# battery_monitor.net
KiCad netlist of a schematic drawn in EAGLE
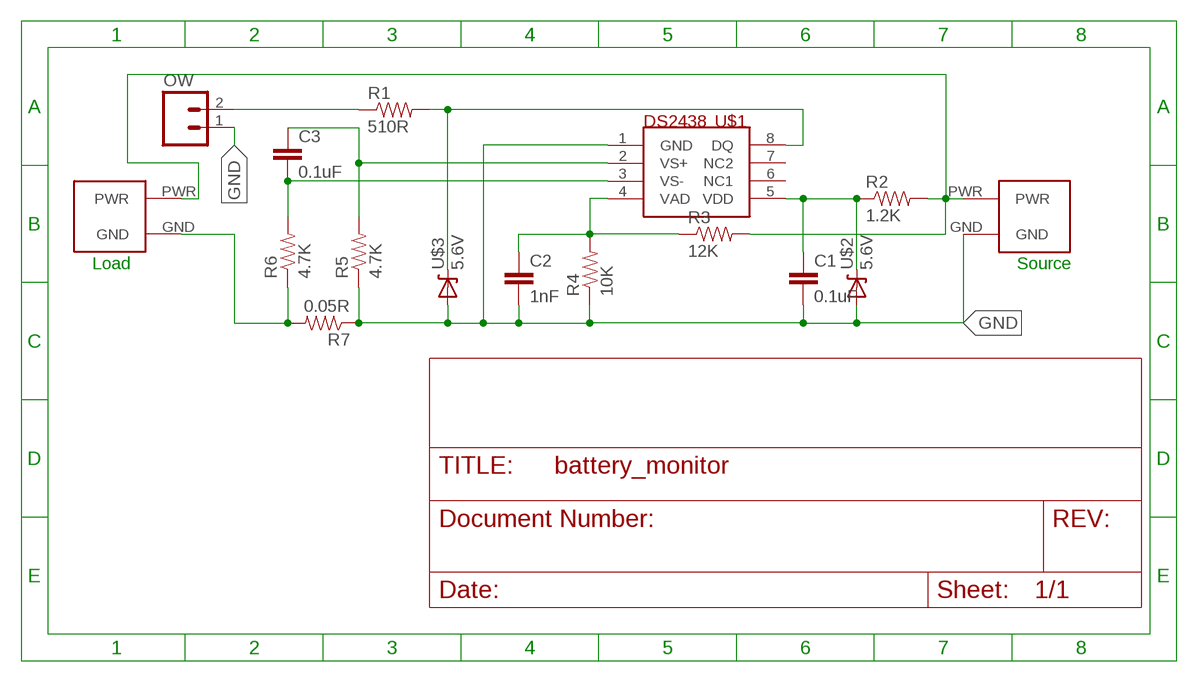
[diagram p0: schematic, sheet 1]

(export (version "E")
  (design (tool "Eeschema 10.0.6"))
  (components
    (comp (ref "C1")
      (value "0.1uF")
      (footprint "eagle-import:0805")
      (libsource (lib "eagle-import") (part "CAP0805"))
    )
    (comp (ref "C2")
      (value "1nF")
      (footprint "eagle-import:0805")
      (libsource (lib "eagle-import") (part "CAP0805"))
    )
    (comp (ref "C3")
      (value "0.1uF")
      (footprint "eagle-import:0805")
      (libsource (lib "eagle-import") (part "CAP0805"))
    )
    (comp (ref "LOAD")
      (value "AND_PWR")
      (footprint "eagle-import:AND_PWR")
      (libsource (lib "eagle-import") (part "AND_PWR"))
    )
    (comp (ref "OW")
      (value "M02POLAR_LOCK")
      (footprint "eagle-import:MOLEX-1X2_LOCK")
      (libsource (lib "eagle-import") (part "M02POLAR_LOCK"))
    )
    (comp (ref "R1")
      (value "510R")
      (footprint "eagle-import:0805")
      (libsource (lib "eagle-import") (part "RESISTOR0805-RES"))
    )
    (comp (ref "R2")
      (value "1.2K")
      (footprint "eagle-import:0805")
      (libsource (lib "eagle-import") (part "RESISTOR0805-RES"))
    )
    (comp (ref "R3")
      (value "12K")
      (footprint "eagle-import:0805")
      (libsource (lib "eagle-import") (part "RESISTOR0805-RES"))
    )
    (comp (ref "R4")
      (value "10K")
      (footprint "eagle-import:0805")
      (libsource (lib "eagle-import") (part "RESISTOR0805-RES"))
    )
    (comp (ref "R5")
      (value "4.7K")
      (footprint "eagle-import:0805")
      (libsource (lib "eagle-import") (part "RESISTOR0805-RES"))
    )
    (comp (ref "R6")
      (value "4.7K")
      (footprint "eagle-import:0805")
      (libsource (lib "eagle-import") (part "RESISTOR0805-RES"))
    )
    (comp (ref "R7")
      (value "0.05R")
      (footprint "eagle-import:1206")
      (libsource (lib "eagle-import") (part "RESISTOR1206"))
    )
    (comp (ref "SOURCE")
      (value "AND_PWR")
      (footprint "eagle-import:AND_PWR")
      (libsource (lib "eagle-import") (part "AND_PWR"))
    )
    (comp (ref "U$1")
      (value "DS2438Z")
      (footprint "eagle-import:SOIC8")
      (libsource (lib "eagle-import") (part "DS2438Z"))
    )
    (comp (ref "U$2")
      (value "5.6V")
      (footprint "eagle-import:SMB-DIODE")
      (libsource (lib "eagle-import") (part "DIODE-ZENERSMB"))
    )
    (comp (ref "U$3")
      (value "5.6V")
      (footprint "eagle-import:SMB-DIODE")
      (libsource (lib "eagle-import") (part "DIODE-ZENERSMB"))
    )
  )
  (nets
    (net (code "1") (name "GND") (class "Default")
      (node (ref "C1") (pin "2") (pinfunction "2_2") (pintype "passive"))
      (node (ref "C2") (pin "2") (pinfunction "2_2") (pintype "passive"))
      (node (ref "OW") (pin "1") (pinfunction "1_1") (pintype "passive"))
      (node (ref "R4") (pin "1") (pinfunction "1_1") (pintype "passive"))
      (node (ref "R5") (pin "1") (pinfunction "1_1") (pintype "passive"))
      (node (ref "R7") (pin "1") (pinfunction "1_1") (pintype "passive"))
      (node (ref "SOURCE") (pin "GND") (pinfunction "GND_GND") (pintype "bidirectional"))
      (node (ref "U$1") (pin "1") (pinfunction "GND_1") (pintype "power_in"))
      (node (ref "U$2") (pin "A") (pinfunction "A_A") (pintype "passive"))
      (node (ref "U$3") (pin "A") (pinfunction "A_A") (pintype "passive"))
    )
    (net (code "2") (name "Net-(LOAD-PadGND)") (class "Default")
      (node (ref "LOAD") (pin "GND") (pinfunction "GND_GND") (pintype "bidirectional"))
      (node (ref "R6") (pin "1") (pinfunction "1_1") (pintype "passive"))
      (node (ref "R7") (pin "2") (pinfunction "2_2") (pintype "passive"))
    )
    (net (code "3") (name "Net-(LOAD-PadPWR)") (class "Default")
      (node (ref "LOAD") (pin "PWR") (pinfunction "PWR_PWR") (pintype "bidirectional"))
      (node (ref "R2") (pin "2") (pinfunction "2_2") (pintype "passive"))
      (node (ref "R3") (pin "2") (pinfunction "2_2") (pintype "passive"))
      (node (ref "SOURCE") (pin "PWR") (pinfunction "PWR_PWR") (pintype "bidirectional"))
    )
    (net (code "4") (name "Net-(OW-Pad2)") (class "Default")
      (node (ref "OW") (pin "2") (pinfunction "2_2") (pintype "passive"))
      (node (ref "R1") (pin "1") (pinfunction "1_1") (pintype "passive"))
    )
    (net (code "5") (name "Net-(U$1-DQ)") (class "Default")
      (node (ref "R1") (pin "2") (pinfunction "2_2") (pintype "passive"))
      (node (ref "U$1") (pin "8") (pinfunction "DQ_8") (pintype "bidirectional"))
      (node (ref "U$3") (pin "C") (pinfunction "C_C") (pintype "passive"))
    )
    (net (code "6") (name "Net-(U$1-VAD)") (class "Default")
      (node (ref "C2") (pin "1") (pinfunction "1_1") (pintype "passive"))
      (node (ref "R3") (pin "1") (pinfunction "1_1") (pintype "passive"))
      (node (ref "R4") (pin "2") (pinfunction "2_2") (pintype "passive"))
      (node (ref "U$1") (pin "4") (pinfunction "VAD_4") (pintype "bidirectional"))
    )
    (net (code "7") (name "Net-(U$1-VDD)") (class "Default")
      (node (ref "C1") (pin "1") (pinfunction "1_1") (pintype "passive"))
      (node (ref "R2") (pin "1") (pinfunction "1_1") (pintype "passive"))
      (node (ref "U$1") (pin "5") (pinfunction "VDD_5") (pintype "power_in"))
      (node (ref "U$2") (pin "C") (pinfunction "C_C") (pintype "passive"))
    )
    (net (code "8") (name "Net-(U$1-VS+)") (class "Default")
      (node (ref "C3") (pin "1") (pinfunction "1_1") (pintype "passive"))
      (node (ref "R5") (pin "2") (pinfunction "2_2") (pintype "passive"))
      (node (ref "U$1") (pin "2") (pinfunction "VS+_2") (pintype "bidirectional"))
    )
    (net (code "9") (name "Net-(U$1-VS-)") (class "Default")
      (node (ref "C3") (pin "2") (pinfunction "2_2") (pintype "passive"))
      (node (ref "R6") (pin "2") (pinfunction "2_2") (pintype "passive"))
      (node (ref "U$1") (pin "3") (pinfunction "VS-_3") (pintype "bidirectional"))
    )
    (net (code "10") (name "unconnected-(U$1-NC1-Pad6)") (class "Default")
      (node (ref "U$1") (pin "6") (pinfunction "NC1_6") (pintype "no_connect"))
    )
    (net (code "11") (name "unconnected-(U$1-NC2-Pad7)") (class "Default")
      (node (ref "U$1") (pin "7") (pinfunction "NC2_7") (pintype "no_connect"))
    )
  )
)
